# Intan_RHS2116.net
KiCad netlist of a schematic drawn in Altium Designer
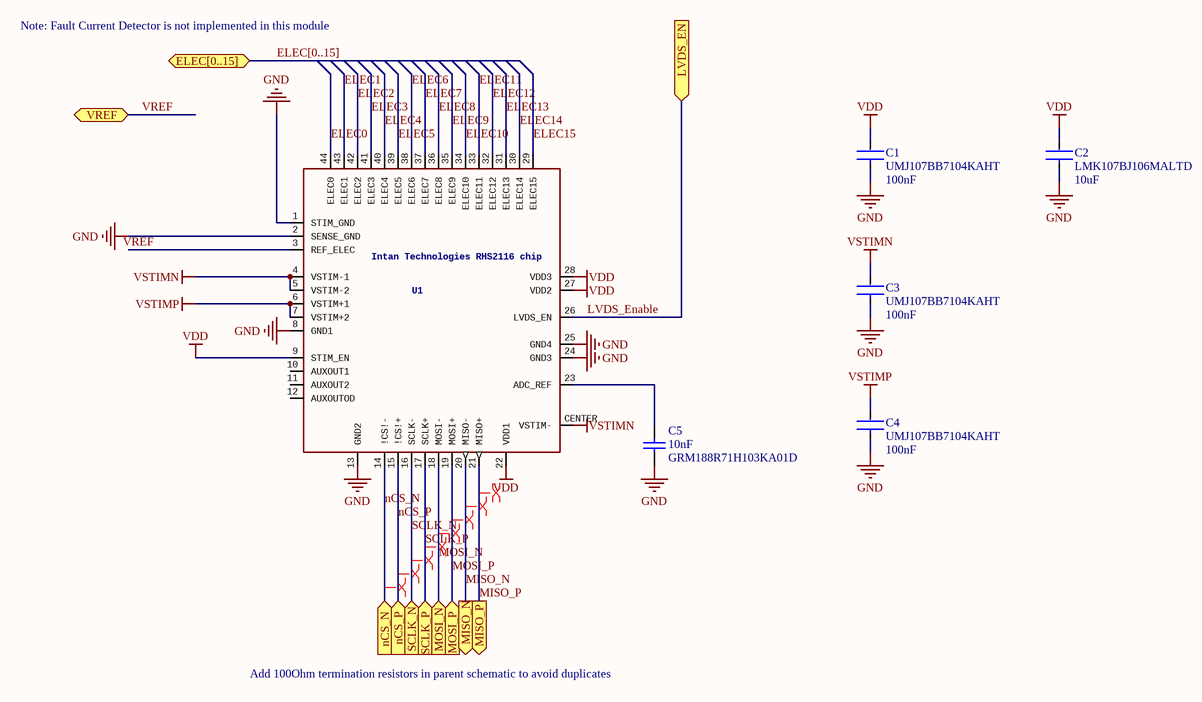
[diagram p0: Intan_RHS2116.SchDoc]

(export (version "E")
  (design (tool "Eeschema 10.0.6"))
  (components
    (comp (ref "C1")
      (value "UMJ107BB7104KAHT")
      (footprint "FP-0603-L_1_6_0_2-W_0_8_0-IPC_B")
      (description "Multilayer Ceramic Capacitor 0.1uF 50V X7R 10% SMD 0603 T/R")
      (fields (field (name "TOLERANCE") "10%") (field (name "CAPACITANCE") "100nF"))
      (libsource (lib "Altium Content Vault") (part "b4654b650e69147ec39a6b967a45e02"))
    )
    (comp (ref "C2")
      (value "LMK107BJ106MALTD")
      (footprint "FP-LMK107BJ106MALTD-IPC_B")
      (description "CAP CER 10UF 10V X5R 0603")
      (fields (field (name "TOLERANCE") "20%") (field (name "CAPACITANCE") "10uF"))
      (libsource (lib "Altium Content Vault") (part "b4654b650e69147ec39a6b967a45e02"))
    )
    (comp (ref "C3")
      (value "UMJ107BB7104KAHT")
      (footprint "FP-0603-L_1_6_0_2-W_0_8_0-IPC_B")
      (description "Multilayer Ceramic Capacitor 0.1uF 50V X7R 10% SMD 0603 T/R")
      (fields (field (name "TOLERANCE") "10%") (field (name "CAPACITANCE") "100nF"))
      (libsource (lib "Altium Content Vault") (part "b4654b650e69147ec39a6b967a45e02"))
    )
    (comp (ref "C4")
      (value "UMJ107BB7104KAHT")
      (footprint "FP-0603-L_1_6_0_2-W_0_8_0-IPC_B")
      (description "Multilayer Ceramic Capacitor 0.1uF 50V X7R 10% SMD 0603 T/R")
      (fields (field (name "TOLERANCE") "10%") (field (name "CAPACITANCE") "100nF"))
      (libsource (lib "Altium Content Vault") (part "b4654b650e69147ec39a6b967a45e02"))
    )
    (comp (ref "C5")
      (value "GRM188R71H103KA01D")
      (footprint "CAPC1608X90X35ML10T15")
      (description "Chip Capacitor, 10 nF, +/- 10%, 50 V, -55 to 125 degC, 0603 (1608 Metric), RoHS, Tape and Reel")
      (fields
        (field (name "VOLTAGE") "50V")
        (field (name "TOLERANCE") "10%")
        (field (name "CAPACITANCE") "10nF")
      )
      (libsource (lib "Altium Content Vault") (part "CAP-NP-2"))
    )
    (comp (ref "U1")
      (value "Intan Technologies RHS2116 chip")
      (footprint "intan_rhs2116:QFN44_7_X_7")
      (fields
        (field (name "MANUFACTURER") "Intan Technologies")
        (field (name "MANUFACTURER PART NUMBER") "RHS2116")
      )
      (libsource (lib "intan_rhs2116") (part "RHS2116_QFN"))
    )
  )
  (nets
    (net (code "1") (name "/ELEC0") (class "Default")
      (node (ref "U1") (pin "44") (pinfunction "ELEC0_44") (pintype "passive"))
    )
    (net (code "2") (name "/ELEC1") (class "Default")
      (node (ref "U1") (pin "43") (pinfunction "ELEC1_43") (pintype "passive"))
    )
    (net (code "3") (name "/ELEC2") (class "Default")
      (node (ref "U1") (pin "42") (pinfunction "ELEC2_42") (pintype "passive"))
    )
    (net (code "4") (name "/ELEC3") (class "Default")
      (node (ref "U1") (pin "41") (pinfunction "ELEC3_41") (pintype "passive"))
    )
    (net (code "5") (name "/ELEC4") (class "Default")
      (node (ref "U1") (pin "40") (pinfunction "ELEC4_40") (pintype "passive"))
    )
    (net (code "6") (name "/ELEC5") (class "Default")
      (node (ref "U1") (pin "39") (pinfunction "ELEC5_39") (pintype "passive"))
    )
    (net (code "7") (name "/ELEC6") (class "Default")
      (node (ref "U1") (pin "38") (pinfunction "ELEC6_38") (pintype "passive"))
    )
    (net (code "8") (name "/ELEC7") (class "Default")
      (node (ref "U1") (pin "37") (pinfunction "ELEC7_37") (pintype "passive"))
    )
    (net (code "9") (name "/ELEC8") (class "Default")
      (node (ref "U1") (pin "36") (pinfunction "ELEC8_36") (pintype "passive"))
    )
    (net (code "10") (name "/ELEC9") (class "Default")
      (node (ref "U1") (pin "35") (pinfunction "ELEC9_35") (pintype "passive"))
    )
    (net (code "11") (name "/ELEC10") (class "Default")
      (node (ref "U1") (pin "34") (pinfunction "ELEC10_34") (pintype "passive"))
    )
    (net (code "12") (name "/ELEC11") (class "Default")
      (node (ref "U1") (pin "33") (pinfunction "ELEC11_33") (pintype "passive"))
    )
    (net (code "13") (name "/ELEC12") (class "Default")
      (node (ref "U1") (pin "32") (pinfunction "ELEC12_32") (pintype "passive"))
    )
    (net (code "14") (name "/ELEC13") (class "Default")
      (node (ref "U1") (pin "31") (pinfunction "ELEC13_31") (pintype "passive"))
    )
    (net (code "15") (name "/ELEC14") (class "Default")
      (node (ref "U1") (pin "30") (pinfunction "ELEC14_30") (pintype "passive"))
    )
    (net (code "16") (name "/ELEC15") (class "Default")
      (node (ref "U1") (pin "29") (pinfunction "ELEC15_29") (pintype "passive"))
    )
    (net (code "18") (name "/LVDS_Enable") (class "Default")
      (node (ref "U1") (pin "26") (pinfunction "LVDS_EN_26") (pintype "passive"))
    )
    (net (code "19") (name "/MISO_N") (class "Default")
      (node (ref "U1") (pin "20") (pinfunction "MISO-_20") (pintype "output"))
    )
    (net (code "20") (name "/MISO_P") (class "Default")
      (node (ref "U1") (pin "21") (pinfunction "MISO+_21") (pintype "output"))
    )
    (net (code "21") (name "/MOSI_N") (class "Default")
      (node (ref "U1") (pin "18") (pinfunction "MOSI-_18") (pintype "passive"))
    )
    (net (code "22") (name "/MOSI_P") (class "Default")
      (node (ref "U1") (pin "19") (pinfunction "MOSI+_19") (pintype "passive"))
    )
    (net (code "23") (name "/SCLK_N") (class "Default")
      (node (ref "U1") (pin "16") (pinfunction "SCLK-_16") (pintype "passive"))
    )
    (net (code "24") (name "/SCLK_P") (class "Default")
      (node (ref "U1") (pin "17") (pinfunction "SCLK+_17") (pintype "passive"))
    )
    (net (code "25") (name "/VREF") (class "Default")
      (node (ref "U1") (pin "3") (pinfunction "REF_ELEC_3") (pintype "passive"))
    )
    (net (code "26") (name "/nCS_N") (class "Default")
      (node (ref "U1") (pin "14") (pinfunction "!CS!-_14") (pintype "passive"))
    )
    (net (code "27") (name "/nCS_P") (class "Default")
      (node (ref "U1") (pin "15") (pinfunction "!CS!+_15") (pintype "passive"))
    )
    (net (code "28") (name "GND") (class "Default")
      (node (ref "C1") (pin "1") (pinfunction "1_1") (pintype "passive"))
      (node (ref "C2") (pin "1") (pinfunction "1_1") (pintype "passive"))
      (node (ref "C3") (pin "1") (pinfunction "1_1") (pintype "passive"))
      (node (ref "C4") (pin "1") (pinfunction "1_1") (pintype "passive"))
      (node (ref "C5") (pin "1") (pinfunction "1_1") (pintype "passive"))
      (node (ref "U1") (pin "1") (pinfunction "STIM_GND_1") (pintype "power_in"))
      (node (ref "U1") (pin "13") (pinfunction "GND2_13") (pintype "power_in"))
      (node (ref "U1") (pin "2") (pinfunction "SENSE_GND_2") (pintype "power_in"))
      (node (ref "U1") (pin "24") (pinfunction "GND3_24") (pintype "power_in"))
      (node (ref "U1") (pin "25") (pinfunction "GND4_25") (pintype "power_in"))
      (node (ref "U1") (pin "8") (pinfunction "GND1_8") (pintype "power_in"))
    )
    (net (code "29") (name "Net-(U1-ADC_REF)") (class "Default")
      (node (ref "C5") (pin "2") (pinfunction "2_2") (pintype "passive"))
      (node (ref "U1") (pin "23") (pinfunction "ADC_REF_23") (pintype "passive"))
    )
    (net (code "30") (name "VDD") (class "Default")
      (node (ref "C1") (pin "2") (pinfunction "2_2") (pintype "passive"))
      (node (ref "C2") (pin "2") (pinfunction "2_2") (pintype "passive"))
      (node (ref "U1") (pin "22") (pinfunction "VDD1_22") (pintype "power_in"))
      (node (ref "U1") (pin "27") (pinfunction "VDD2_27") (pintype "power_in"))
      (node (ref "U1") (pin "28") (pinfunction "VDD3_28") (pintype "power_in"))
      (node (ref "U1") (pin "9") (pinfunction "STIM_EN_9") (pintype "passive"))
    )
    (net (code "31") (name "VSTIMN") (class "Default")
      (node (ref "C3") (pin "2") (pinfunction "2_2") (pintype "passive"))
      (node (ref "U1") (pin "4") (pinfunction "VSTIM-1_4") (pintype "power_in"))
      (node (ref "U1") (pin "5") (pinfunction "VSTIM-2_5") (pintype "power_in"))
      (node (ref "U1") (pin "CENTER") (pinfunction "VSTIM-_CENTER") (pintype "power_in"))
    )
    (net (code "32") (name "VSTIMP") (class "Default")
      (node (ref "C4") (pin "2") (pinfunction "2_2") (pintype "passive"))
      (node (ref "U1") (pin "6") (pinfunction "VSTIM+1_6") (pintype "power_in"))
      (node (ref "U1") (pin "7") (pinfunction "VSTIM+2_7") (pintype "power_in"))
    )
    (net (code "33") (name "unconnected-(U1-AUXOUT1-Pad10)") (class "Default")
      (node (ref "U1") (pin "10") (pinfunction "AUXOUT1_10") (pintype "tri_state"))
    )
    (net (code "34") (name "unconnected-(U1-AUXOUT2-Pad11)") (class "Default")
      (node (ref "U1") (pin "11") (pinfunction "AUXOUT2_11") (pintype "tri_state"))
    )
    (net (code "35") (name "unconnected-(U1-AUXOUTOD-Pad12)") (class "Default")
      (node (ref "U1") (pin "12") (pinfunction "AUXOUTOD_12") (pintype "open_collector"))
    )
  )
)
